# LSM6DS3TR-C.net
KiCad netlist of a schematic drawn in Altium Designer
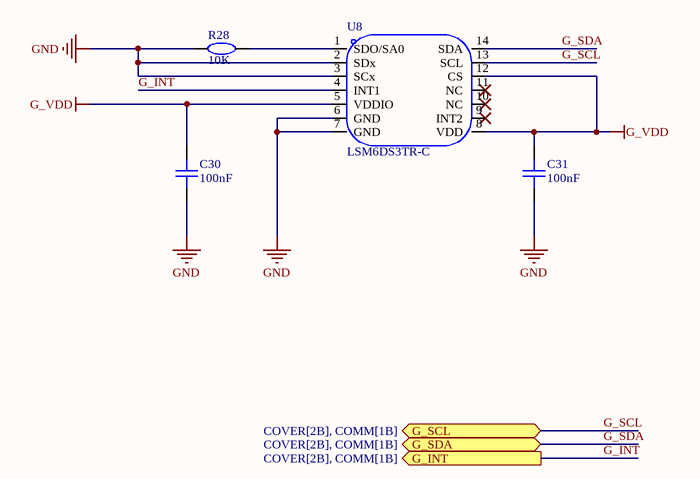
[diagram p0: LSM6DS3TR-C.SchDoc]

(export (version "E")
  (design (tool "Eeschema 10.0.6"))
  (components
    (comp (ref "C30")
      (value "100nF")
      (footprint "C0402")
      (fields (field (name "NAME") "100nF"))
      (libsource (lib "my_library") (part "CAP_0402"))
    )
    (comp (ref "C31")
      (value "100nF")
      (footprint "C0402")
      (fields (field (name "NAME") "100nF"))
      (libsource (lib "my_library") (part "CAP_0402"))
    )
    (comp (ref "R28")
      (value "10K")
      (footprint "R0402")
      (fields (field (name "NAME") "10K"))
      (libsource (lib "my_library") (part "Res_0402"))
    )
    (comp (ref "U8")
      (value "LSM6DS3TR-C")
      (footprint "LGA-14_L3.0-W2.5-P0.50-TL")
      (fields (field (name "MANUFACTURER") "ST(意法半导体)") (field (name "NAME") "LSM6DS3TR-C"))
      (libsource (lib "my_library") (part "LSM6DS3TR-C"))
    )
  )
  (nets
    (net (code "1") (name "/G_INT") (class "Default")
      (node (ref "U8") (pin "4") (pinfunction "INT1_4") (pintype "passive"))
    )
    (net (code "2") (name "/G_SCL") (class "Default")
      (node (ref "U8") (pin "13") (pinfunction "SCL_13") (pintype "passive"))
    )
    (net (code "3") (name "/G_SDA") (class "Default")
      (node (ref "U8") (pin "14") (pinfunction "SDA_14") (pintype "passive"))
    )
    (net (code "4") (name "GND") (class "Default")
      (node (ref "C30") (pin "1") (pinfunction "1_1") (pintype "passive"))
      (node (ref "C31") (pin "1") (pinfunction "1_1") (pintype "passive"))
      (node (ref "R28") (pin "1") (pinfunction "1_1") (pintype "passive"))
      (node (ref "U8") (pin "2") (pinfunction "SDx_2") (pintype "passive"))
      (node (ref "U8") (pin "3") (pinfunction "SCx_3") (pintype "passive"))
      (node (ref "U8") (pin "6") (pinfunction "GND_6") (pintype "passive"))
      (node (ref "U8") (pin "7") (pinfunction "GND_7") (pintype "passive"))
    )
    (net (code "5") (name "G_VDD") (class "Default")
      (node (ref "C30") (pin "2") (pinfunction "2_2") (pintype "passive"))
      (node (ref "C31") (pin "2") (pinfunction "2_2") (pintype "passive"))
      (node (ref "U8") (pin "12") (pinfunction "CS_12") (pintype "passive"))
      (node (ref "U8") (pin "5") (pinfunction "VDDIO_5") (pintype "passive"))
      (node (ref "U8") (pin "8") (pinfunction "VDD_8") (pintype "passive"))
    )
    (net (code "6") (name "Net-(U8-SDO{slash}SA0)") (class "Default")
      (node (ref "R28") (pin "2") (pinfunction "2_2") (pintype "passive"))
      (node (ref "U8") (pin "1") (pinfunction "SDO/SA0_1") (pintype "passive"))
    )
    (net (code "7") (name "unconnected-(U8-INT2-Pad9)") (class "Default")
      (node (ref "U8") (pin "9") (pinfunction "INT2_9") (pintype "passive+no_connect"))
    )
    (net (code "8") (name "unconnected-(U8-NC-Pad10)") (class "Default")
      (node (ref "U8") (pin "10") (pinfunction "NC_10") (pintype "passive+no_connect"))
    )
    (net (code "9") (name "unconnected-(U8-NC-Pad11)") (class "Default")
      (node (ref "U8") (pin "11") (pinfunction "NC_11") (pintype "passive+no_connect"))
    )
  )
)
